# ball_catch_unit_front.net
KiCad netlist of a schematic drawn in EAGLE
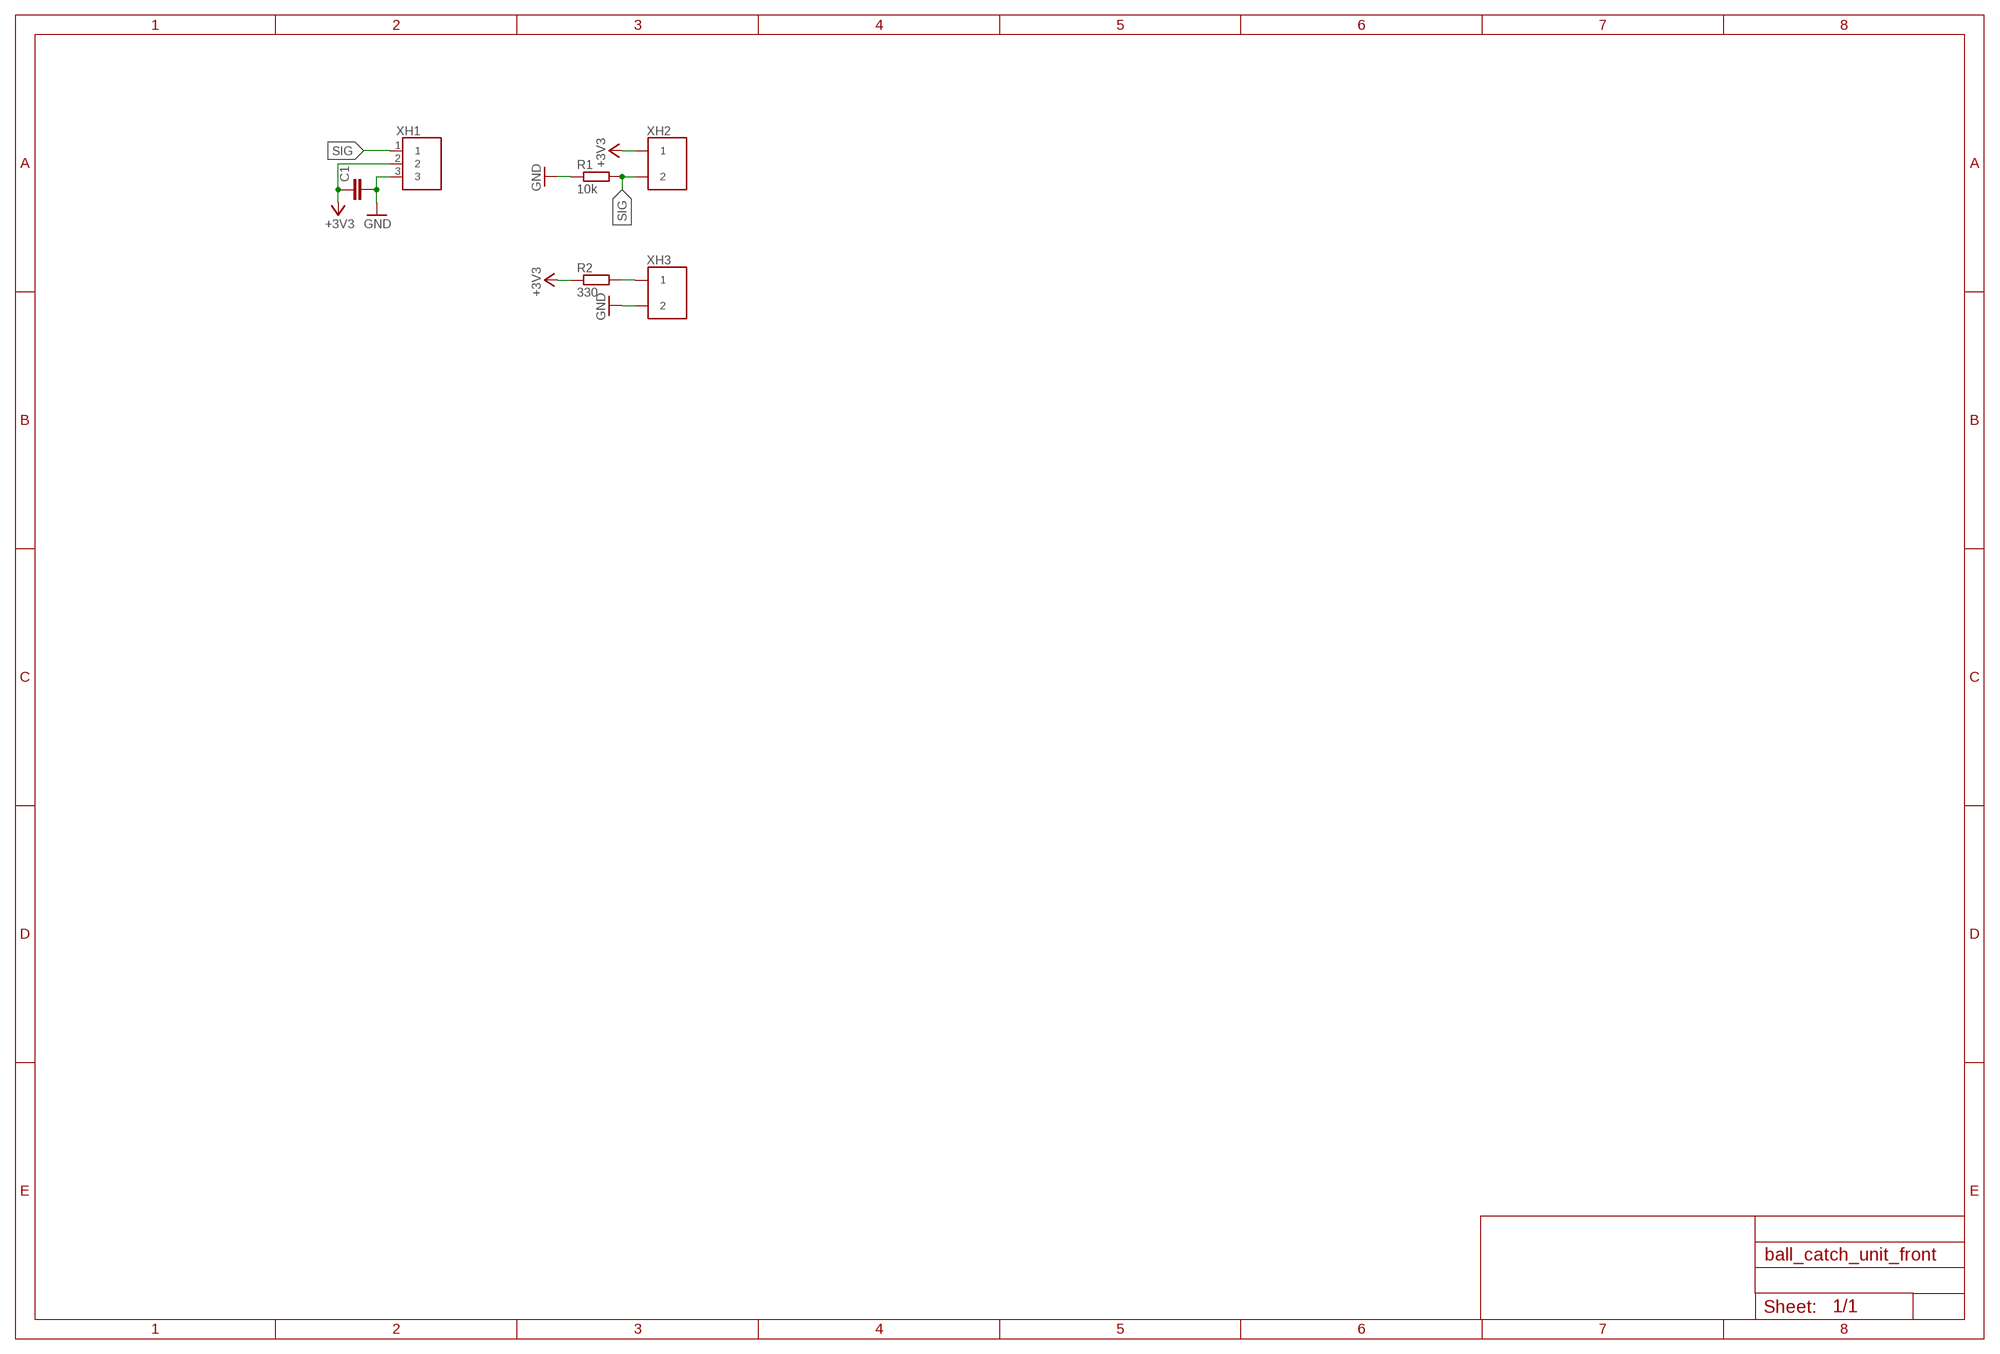
[diagram p0: schematic, sheet 1]

(export (version "E")
  (design (tool "Eeschema 10.0.6"))
  (components
    (comp (ref "C1")
      (value "C-EUC0603")
      (footprint "eagle-import:C0603")
      (libsource (lib "eagle-import") (part "C-EUC0603"))
    )
    (comp (ref "R1")
      (value "10k")
      (footprint "eagle-import:0204_7")
      (libsource (lib "eagle-import") (part "R-EU_0204/7"))
    )
    (comp (ref "R2")
      (value "330")
      (footprint "eagle-import:0204_7")
      (libsource (lib "eagle-import") (part "R-EU_0204/7"))
    )
    (comp (ref "XH1")
      (value "S3B")
      (footprint "eagle-import:S3B")
      (libsource (lib "eagle-import") (part "S3B"))
    )
    (comp (ref "XH2") (value "2B") (footprint "eagle-import:2B") (libsource (lib "eagle-import") (part "2B")))
    (comp (ref "XH3")
      (value "S2B")
      (footprint "eagle-import:S2B")
      (libsource (lib "eagle-import") (part "S2B"))
    )
  )
  (nets
    (net (code "1") (name "+3V3") (class "Default")
      (node (ref "C1") (pin "1") (pinfunction "1_1") (pintype "passive"))
      (node (ref "R2") (pin "1") (pinfunction "1_1") (pintype "passive"))
      (node (ref "XH1") (pin "2") (pinfunction "2_2") (pintype "bidirectional"))
      (node (ref "XH2") (pin "1") (pinfunction "1_1") (pintype "bidirectional"))
    )
    (net (code "2") (name "GND") (class "Default")
      (node (ref "C1") (pin "2") (pinfunction "2_2") (pintype "passive"))
      (node (ref "R1") (pin "1") (pinfunction "1_1") (pintype "passive"))
      (node (ref "XH1") (pin "3") (pinfunction "3_3") (pintype "bidirectional"))
      (node (ref "XH3") (pin "2") (pinfunction "2_2") (pintype "bidirectional"))
    )
    (net (code "3") (name "Net-(R2-Pad2)") (class "Default")
      (node (ref "R2") (pin "2") (pinfunction "2_2") (pintype "passive"))
      (node (ref "XH3") (pin "1") (pinfunction "1_1") (pintype "bidirectional"))
    )
    (net (code "4") (name "SIG") (class "Default")
      (node (ref "R1") (pin "2") (pinfunction "2_2") (pintype "passive"))
      (node (ref "XH1") (pin "1") (pinfunction "1_1") (pintype "bidirectional"))
      (node (ref "XH2") (pin "2") (pinfunction "2_2") (pintype "bidirectional"))
    )
  )
)
